# Power.net
KiCad netlist of a schematic drawn in Altium Designer
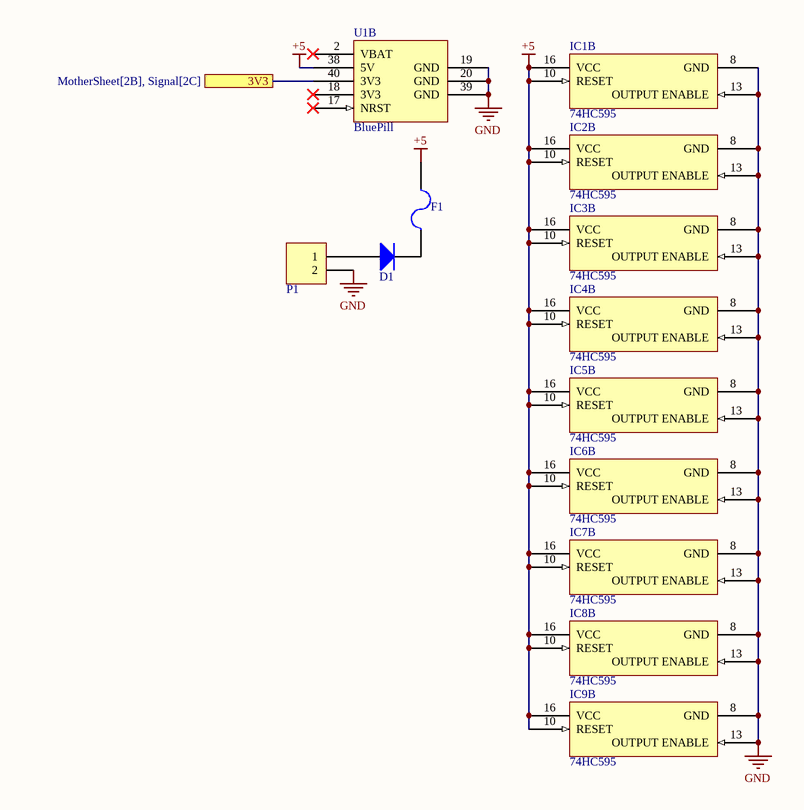
[diagram p0: Power.SchDoc]

(export (version "E")
  (design (tool "Eeschema 10.0.6"))
  (components
    (comp (ref "D1")
      (value "Diode")
      (footprint "D1A")
      (description "Default Diode")
      (libsource (lib "PIF_Library") (part "Diode"))
    )
    (comp (ref "F1") (value "Fuse") (footprint "FUSE SMD") (libsource (lib "PIF_Library") (part "Fuse")))
    (comp (ref "IC1")
      (value "74HC595")
      (footprint "74HC595")
      (libsource (lib "LaBibliothequeDeLongNhong") (part "74HC595"))
    )
    (comp (ref "IC2")
      (value "74HC595")
      (footprint "74HC595")
      (libsource (lib "LaBibliothequeDeLongNhong") (part "74HC595"))
    )
    (comp (ref "IC3")
      (value "74HC595")
      (footprint "74HC595")
      (libsource (lib "LaBibliothequeDeLongNhong") (part "74HC595"))
    )
    (comp (ref "IC4")
      (value "74HC595")
      (footprint "74HC595")
      (libsource (lib "LaBibliothequeDeLongNhong") (part "74HC595"))
    )
    (comp (ref "IC5")
      (value "74HC595")
      (footprint "74HC595")
      (libsource (lib "LaBibliothequeDeLongNhong") (part "74HC595"))
    )
    (comp (ref "IC6")
      (value "74HC595")
      (footprint "74HC595")
      (libsource (lib "LaBibliothequeDeLongNhong") (part "74HC595"))
    )
    (comp (ref "IC7")
      (value "74HC595")
      (footprint "74HC595")
      (libsource (lib "LaBibliothequeDeLongNhong") (part "74HC595"))
    )
    (comp (ref "IC8")
      (value "74HC595")
      (footprint "74HC595")
      (libsource (lib "LaBibliothequeDeLongNhong") (part "74HC595"))
    )
    (comp (ref "IC9")
      (value "74HC595")
      (footprint "74HC595")
      (libsource (lib "LaBibliothequeDeLongNhong") (part "74HC595"))
    )
    (comp (ref "P1")
      (value "Domino 2")
      (footprint "DOMINO 2- 5mm")
      (description "Domino, 2-Pin")
      (fields (field (name "PUBLISHER") "Altium Limited"))
      (libsource (lib "PIF_Library") (part "Domino 2"))
    )
    (comp (ref "U1")
      (value "BluePill")
      (footprint "BluePill")
      (libsource (lib "LaBibliothequeDeLongNhong") (part "BluePill"))
    )
  )
  (nets
    (net (code "1") (name "+5") (class "Default")
      (node (ref "F1") (pin "2") (pinfunction "2_2") (pintype "passive"))
      (node (ref "IC1") (pin "10") (pinfunction "RESET_10") (pintype "input"))
      (node (ref "IC1") (pin "16") (pinfunction "VCC_16") (pintype "power_in"))
      (node (ref "IC2") (pin "10") (pinfunction "RESET_10") (pintype "input"))
      (node (ref "IC2") (pin "16") (pinfunction "VCC_16") (pintype "power_in"))
      (node (ref "IC3") (pin "10") (pinfunction "RESET_10") (pintype "input"))
      (node (ref "IC3") (pin "16") (pinfunction "VCC_16") (pintype "power_in"))
      (node (ref "IC4") (pin "10") (pinfunction "RESET_10") (pintype "input"))
      (node (ref "IC4") (pin "16") (pinfunction "VCC_16") (pintype "power_in"))
      (node (ref "IC5") (pin "10") (pinfunction "RESET_10") (pintype "input"))
      (node (ref "IC5") (pin "16") (pinfunction "VCC_16") (pintype "power_in"))
      (node (ref "IC6") (pin "10") (pinfunction "RESET_10") (pintype "input"))
      (node (ref "IC6") (pin "16") (pinfunction "VCC_16") (pintype "power_in"))
      (node (ref "IC7") (pin "10") (pinfunction "RESET_10") (pintype "input"))
      (node (ref "IC7") (pin "16") (pinfunction "VCC_16") (pintype "power_in"))
      (node (ref "IC8") (pin "10") (pinfunction "RESET_10") (pintype "input"))
      (node (ref "IC8") (pin "16") (pinfunction "VCC_16") (pintype "power_in"))
      (node (ref "IC9") (pin "10") (pinfunction "RESET_10") (pintype "input"))
      (node (ref "IC9") (pin "16") (pinfunction "VCC_16") (pintype "power_in"))
      (node (ref "U1") (pin "38") (pinfunction "5V_38") (pintype "power_in"))
    )
    (net (code "2") (name "/3V3") (class "Default")
      (node (ref "U1") (pin "40") (pinfunction "3V3_40") (pintype "power_in"))
    )
    (net (code "3") (name "GND") (class "Default")
      (node (ref "IC1") (pin "13") (pinfunction "OUTPUT_ENABLE_13") (pintype "input"))
      (node (ref "IC1") (pin "8") (pinfunction "GND_8") (pintype "power_in"))
      (node (ref "IC2") (pin "13") (pinfunction "OUTPUT_ENABLE_13") (pintype "input"))
      (node (ref "IC2") (pin "8") (pinfunction "GND_8") (pintype "power_in"))
      (node (ref "IC3") (pin "13") (pinfunction "OUTPUT_ENABLE_13") (pintype "input"))
      (node (ref "IC3") (pin "8") (pinfunction "GND_8") (pintype "power_in"))
      (node (ref "IC4") (pin "13") (pinfunction "OUTPUT_ENABLE_13") (pintype "input"))
      (node (ref "IC4") (pin "8") (pinfunction "GND_8") (pintype "power_in"))
      (node (ref "IC5") (pin "13") (pinfunction "OUTPUT_ENABLE_13") (pintype "input"))
      (node (ref "IC5") (pin "8") (pinfunction "GND_8") (pintype "power_in"))
      (node (ref "IC6") (pin "13") (pinfunction "OUTPUT_ENABLE_13") (pintype "input"))
      (node (ref "IC6") (pin "8") (pinfunction "GND_8") (pintype "power_in"))
      (node (ref "IC7") (pin "13") (pinfunction "OUTPUT_ENABLE_13") (pintype "input"))
      (node (ref "IC7") (pin "8") (pinfunction "GND_8") (pintype "power_in"))
      (node (ref "IC8") (pin "13") (pinfunction "OUTPUT_ENABLE_13") (pintype "input"))
      (node (ref "IC8") (pin "8") (pinfunction "GND_8") (pintype "power_in"))
      (node (ref "IC9") (pin "13") (pinfunction "OUTPUT_ENABLE_13") (pintype "input"))
      (node (ref "IC9") (pin "8") (pinfunction "GND_8") (pintype "power_in"))
      (node (ref "P1") (pin "2") (pinfunction "2_2") (pintype "passive"))
      (node (ref "U1") (pin "19") (pinfunction "GND_19") (pintype "power_in"))
      (node (ref "U1") (pin "20") (pinfunction "GND_20") (pintype "power_in"))
      (node (ref "U1") (pin "39") (pinfunction "GND_39") (pintype "power_in"))
    )
    (net (code "4") (name "Net-(D1-A)") (class "Default")
      (node (ref "D1") (pin "1") (pinfunction "A_1") (pintype "passive"))
      (node (ref "P1") (pin "1") (pinfunction "1_1") (pintype "passive"))
    )
    (net (code "5") (name "Net-(D1-K)") (class "Default")
      (node (ref "D1") (pin "2") (pinfunction "K_2") (pintype "passive"))
      (node (ref "F1") (pin "1") (pinfunction "1_1") (pintype "passive"))
    )
    (net (code "6") (name "unconnected-(U1B-3V3-Pad18)") (class "Default")
      (node (ref "U1") (pin "18") (pinfunction "3V3_18") (pintype "power_in+no_connect"))
    )
    (net (code "7") (name "unconnected-(U1B-NRST-Pad17)") (class "Default")
      (node (ref "U1") (pin "17") (pinfunction "NRST_17") (pintype "input+no_connect"))
    )
    (net (code "8") (name "unconnected-(U1B-VBAT-Pad2)") (class "Default")
      (node (ref "U1") (pin "2") (pinfunction "VBAT_2") (pintype "power_in+no_connect"))
    )
  )
)
